# sch.net
KiCad netlist of a schematic drawn in EAGLE
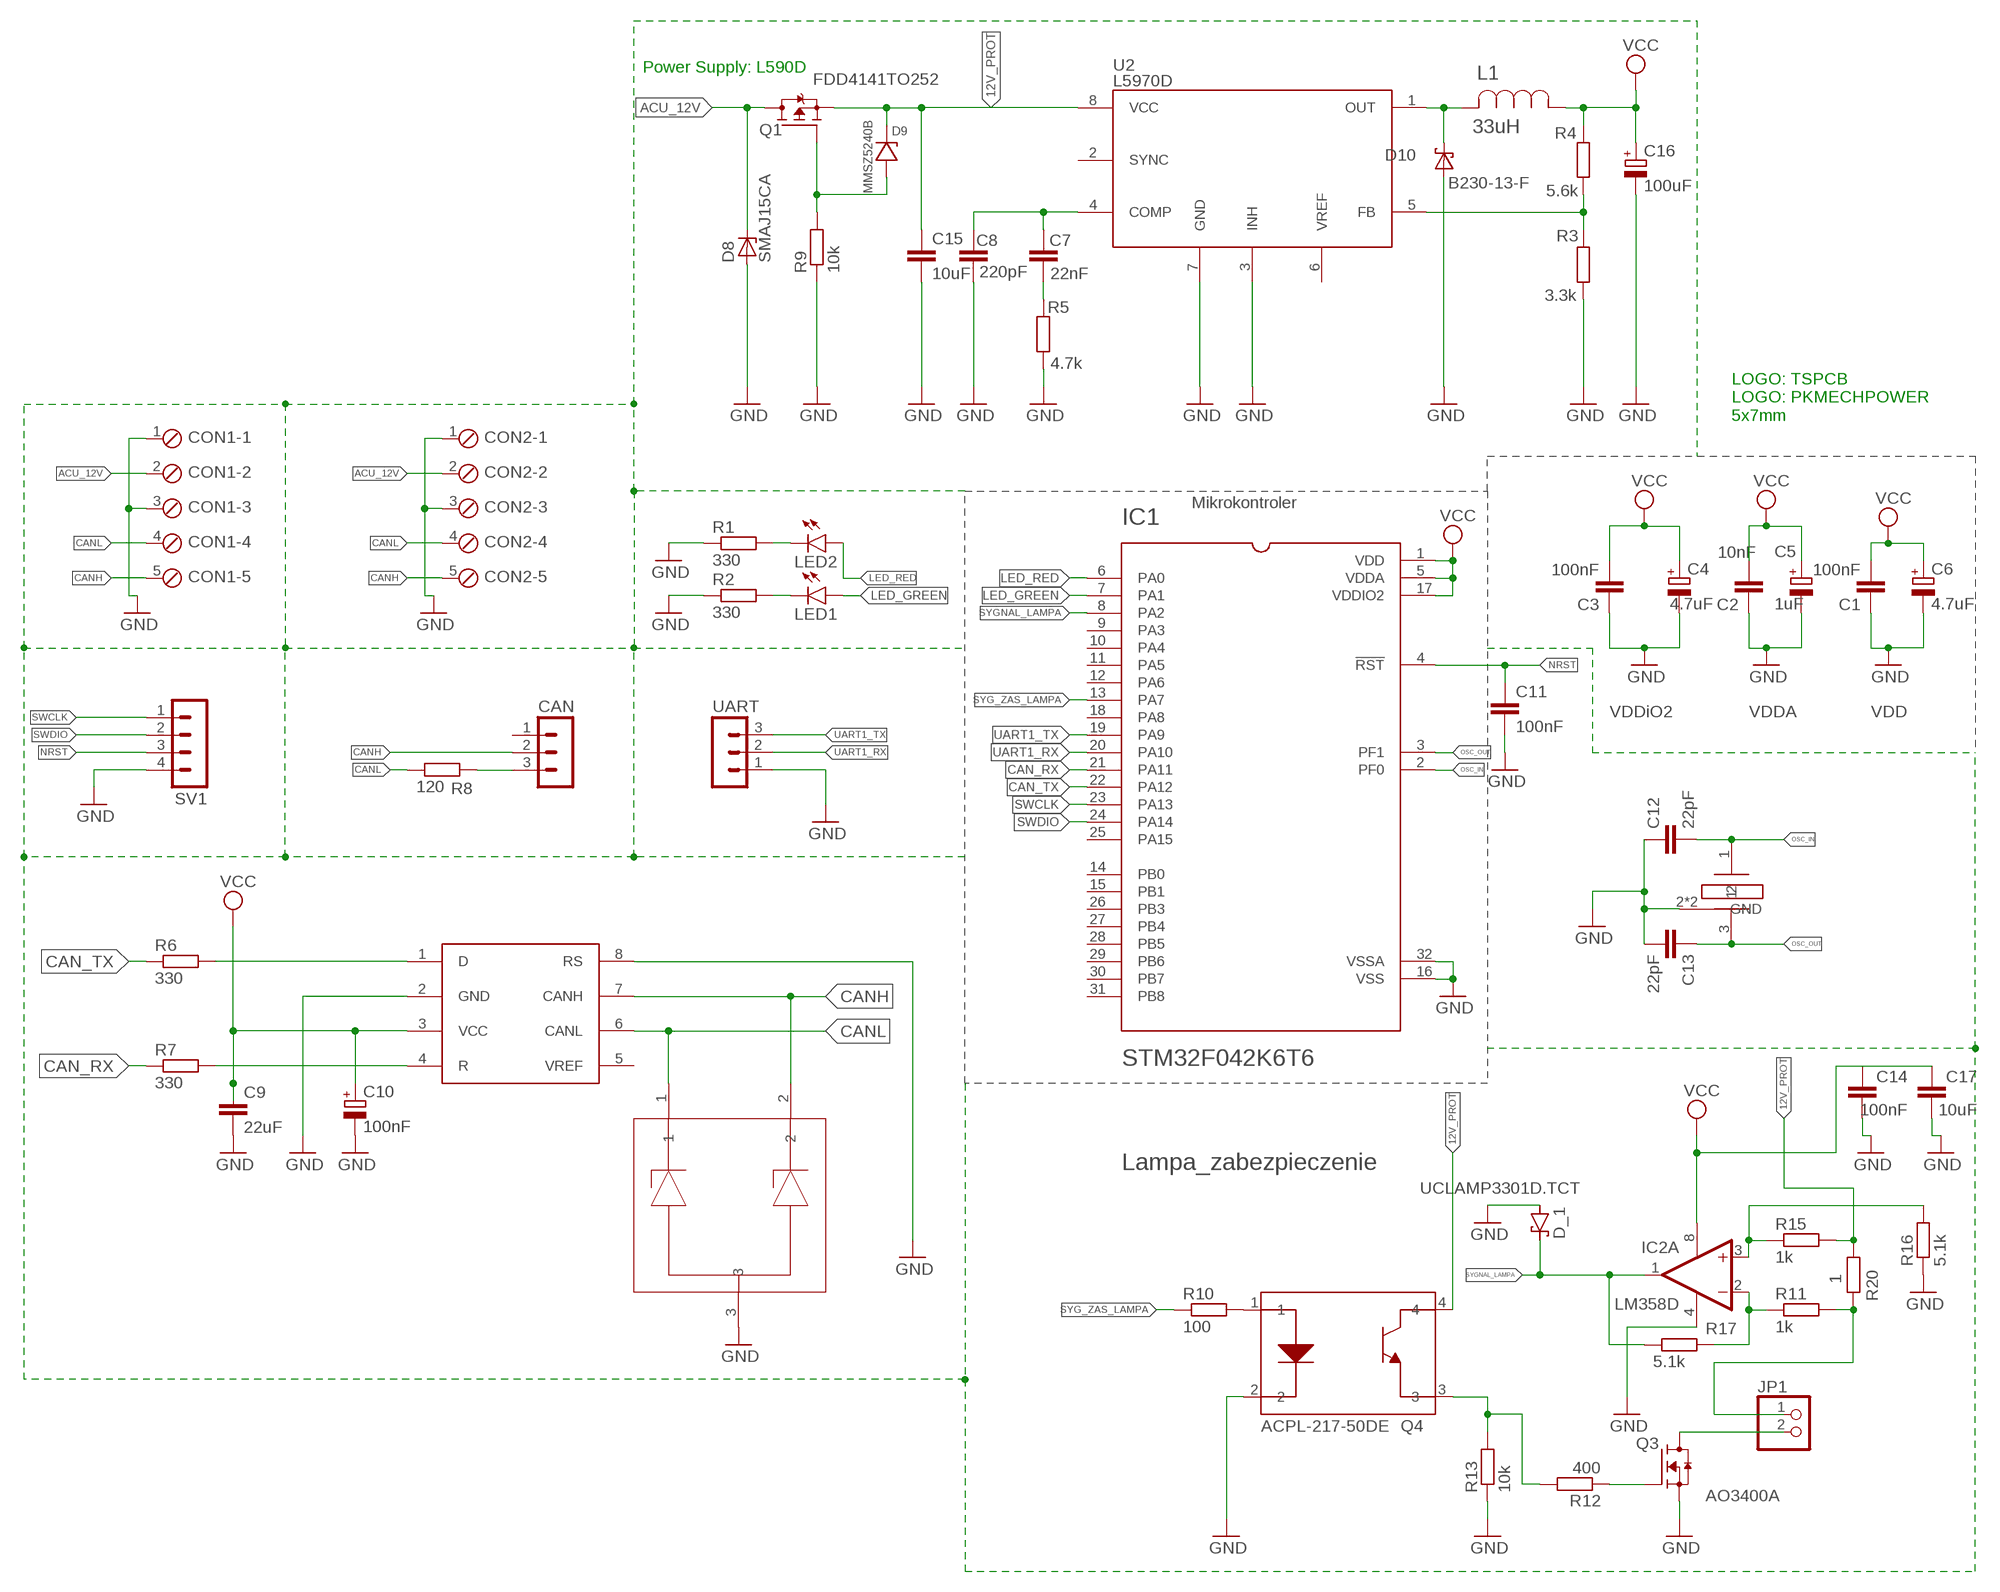
[diagram p0: schematic, sheet 1]

(export (version "E")
  (design (tool "Eeschema 10.0.6"))
  (components
    (comp (ref "C1")
      (value "100nF")
      (footprint "eagle-import:C0805")
      (libsource (lib "eagle-import") (part "C-EUC0805"))
    )
    (comp (ref "C2")
      (value "10nF")
      (footprint "eagle-import:C0805")
      (libsource (lib "eagle-import") (part "C-EUC0805"))
    )
    (comp (ref "C3")
      (value "100nF")
      (footprint "eagle-import:C0805")
      (libsource (lib "eagle-import") (part "C-EUC0805"))
    )
    (comp (ref "C4")
      (value "4.7uF")
      (footprint "eagle-import:SMC_C")
      (libsource (lib "eagle-import") (part "CPOL-EUSMCC"))
    )
    (comp (ref "C5")
      (value "1uF")
      (footprint "eagle-import:SMC_C")
      (libsource (lib "eagle-import") (part "CPOL-EUSMCC"))
    )
    (comp (ref "C6")
      (value "4.7uF")
      (footprint "eagle-import:SMC_C")
      (libsource (lib "eagle-import") (part "CPOL-EUSMCC"))
    )
    (comp (ref "C7")
      (value "22nF")
      (footprint "eagle-import:C0805")
      (libsource (lib "eagle-import") (part "C-EUC0805"))
    )
    (comp (ref "C8")
      (value "220pF")
      (footprint "eagle-import:C0805")
      (libsource (lib "eagle-import") (part "C-EUC0805"))
    )
    (comp (ref "C9")
      (value "22uF")
      (footprint "eagle-import:C0805")
      (libsource (lib "eagle-import") (part "C-EUC0805"))
    )
    (comp (ref "C10")
      (value "100nF")
      (footprint "eagle-import:SMC_C")
      (libsource (lib "eagle-import") (part "CPOL-EUSMCC"))
    )
    (comp (ref "C11")
      (value "100nF")
      (footprint "eagle-import:C0805")
      (libsource (lib "eagle-import") (part "C-EUC0805"))
    )
    (comp (ref "C12")
      (value "22pF")
      (footprint "eagle-import:C0805")
      (libsource (lib "eagle-import") (part "C-EUC0805"))
    )
    (comp (ref "C13")
      (value "22pF")
      (footprint "eagle-import:C0805")
      (libsource (lib "eagle-import") (part "C-EUC0805"))
    )
    (comp (ref "C14")
      (value "100nF")
      (footprint "eagle-import:C0805")
      (libsource (lib "eagle-import") (part "C-EUC0805"))
    )
    (comp (ref "C15")
      (value "10uF")
      (footprint "eagle-import:C1210")
      (libsource (lib "eagle-import") (part "C-EUC1210"))
    )
    (comp (ref "C16")
      (value "100uF")
      (footprint "eagle-import:SMC_D")
      (libsource (lib "eagle-import") (part "CPOL-EUSMCD"))
    )
    (comp (ref "C17")
      (value "10uF")
      (footprint "eagle-import:C0805")
      (libsource (lib "eagle-import") (part "C-EUC0805"))
    )
    (comp (ref "CAN")
      (value "MA03-1")
      (footprint "eagle-import:MA03-1")
      (libsource (lib "eagle-import") (part "MA03-1"))
    )
    (comp (ref "CON1")
      (value "MPT5")
      (footprint "eagle-import:5POL254")
      (libsource (lib "eagle-import") (part "MPT5"))
    )
    (comp (ref "CON2")
      (value "MPT5")
      (footprint "eagle-import:5POL254")
      (libsource (lib "eagle-import") (part "MPT5"))
    )
    (comp (ref "D8")
      (value "SMAJ15CA")
      (footprint "eagle-import:SMA")
      (fields (field (name "MF") "Nexperia USA") (field (name "MP") "PESD5V0X1UB"))
      (libsource (lib "eagle-import") (part "SMAJ15CA"))
    )
    (comp (ref "D9")
      (value "MMSZ5240B")
      (footprint "eagle-import:SOD123")
      (libsource (lib "eagle-import") (part "ZENER_01"))
    )
    (comp (ref "D10")
      (value "B230-13-F")
      (footprint "eagle-import:SMB")
      (libsource (lib "eagle-import") (part "B230-13-F"))
    )
    (comp (ref "D_1")
      (value "UCLAMP3301D.TCT")
      (footprint "eagle-import:SOD323")
      (libsource (lib "eagle-import") (part "UCLAMP3301D.TCT"))
    )
    (comp (ref "IC1")
      (value "STM32F042K6T6")
      (footprint "eagle-import:QFP80P900X900X160-32N")
      (fields (field (name "MF") "STMicroelectronics"))
      (libsource (lib "eagle-import") (part "STM32F042K6T6"))
    )
    (comp (ref "IC2")
      (value "LM358D")
      (footprint "eagle-import:SO08")
      (libsource (lib "eagle-import") (part "LM358D"))
    )
    (comp (ref "JP1")
      (value "PINHD-1X2")
      (footprint "eagle-import:1X02")
      (libsource (lib "eagle-import") (part "PINHD-1X2"))
    )
    (comp (ref "L1")
      (value "33uH")
      (footprint "eagle-import:INDM125125X600N")
      (fields (field (name "MF") "Coilcraft") (field (name "MP") "DR125-680-R"))
      (libsource (lib "eagle-import") (part "DR125-680-R"))
    )
    (comp (ref "LED1")
      (value "LEDCHIP-LED0805")
      (footprint "eagle-import:CHIP-LED0805")
      (libsource (lib "eagle-import") (part "LEDCHIP-LED0805"))
    )
    (comp (ref "LED2")
      (value "LEDCHIP-LED0805")
      (footprint "eagle-import:CHIP-LED0805")
      (libsource (lib "eagle-import") (part "LEDCHIP-LED0805"))
    )
    (comp (ref "Q1")
      (value "FDD4141TO252")
      (footprint "eagle-import:TO252")
      (libsource (lib "eagle-import") (part "FDD4141TO252"))
    )
    (comp (ref "Q3")
      (value "AO3400A")
      (footprint "eagle-import:SOT95P280X125-3N")
      (fields (field (name "MF") "Alpha &"))
      (libsource (lib "eagle-import") (part "AO3400A"))
    )
    (comp (ref "Q4")
      (value "ACPL-217-50DE")
      (footprint "eagle-import:SOIC127P700X220-4N")
      (fields (field (name "MF") "Broadcom / Avago"))
      (libsource (lib "eagle-import") (part "ACPL-217-50DE"))
    )
    (comp (ref "R1")
      (value "330")
      (footprint "eagle-import:R0805")
      (libsource (lib "eagle-import") (part "R-EU_R0805"))
    )
    (comp (ref "R2")
      (value "330")
      (footprint "eagle-import:R0805")
      (libsource (lib "eagle-import") (part "R-EU_R0805"))
    )
    (comp (ref "R3")
      (value "3.3k")
      (footprint "eagle-import:R0805")
      (libsource (lib "eagle-import") (part "R-EU_R0805"))
    )
    (comp (ref "R4")
      (value "5.6k")
      (footprint "eagle-import:R0805")
      (libsource (lib "eagle-import") (part "R-EU_R0805"))
    )
    (comp (ref "R5")
      (value "4.7k")
      (footprint "eagle-import:R0805")
      (libsource (lib "eagle-import") (part "R-EU_R0805"))
    )
    (comp (ref "R6")
      (value "330")
      (footprint "eagle-import:M0805")
      (libsource (lib "eagle-import") (part "R-EU_M0805"))
    )
    (comp (ref "R7")
      (value "330")
      (footprint "eagle-import:M0805")
      (libsource (lib "eagle-import") (part "R-EU_M0805"))
    )
    (comp (ref "R8")
      (value "120")
      (footprint "eagle-import:M0805")
      (libsource (lib "eagle-import") (part "R-EU_M0805"))
    )
    (comp (ref "R9")
      (value "10k")
      (footprint "eagle-import:R0805")
      (libsource (lib "eagle-import") (part "R-EU_R0805"))
    )
    (comp (ref "R10")
      (value "100")
      (footprint "eagle-import:M0805")
      (libsource (lib "eagle-import") (part "R-EU_M0805"))
    )
    (comp (ref "R11")
      (value "1k")
      (footprint "eagle-import:M0805")
      (libsource (lib "eagle-import") (part "R-EU_M0805"))
    )
    (comp (ref "R12")
      (value "400")
      (footprint "eagle-import:M0805")
      (libsource (lib "eagle-import") (part "R-EU_M0805"))
    )
    (comp (ref "R13")
      (value "10k")
      (footprint "eagle-import:M0805")
      (libsource (lib "eagle-import") (part "R-EU_M0805"))
    )
    (comp (ref "R15")
      (value "1k")
      (footprint "eagle-import:M0805")
      (libsource (lib "eagle-import") (part "R-EU_M0805"))
    )
    (comp (ref "R16")
      (value "5.1k")
      (footprint "eagle-import:M0805")
      (libsource (lib "eagle-import") (part "R-EU_M0805"))
    )
    (comp (ref "R17")
      (value "5.1k")
      (footprint "eagle-import:M0805")
      (libsource (lib "eagle-import") (part "R-EU_M0805"))
    )
    (comp (ref "R20")
      (value "1")
      (footprint "eagle-import:R2512")
      (libsource (lib "eagle-import") (part "R-EU_R2512"))
    )
    (comp (ref "SV1")
      (value "MA04-1")
      (footprint "eagle-import:MA04-1")
      (libsource (lib "eagle-import") (part "MA04-1"))
    )
    (comp (ref "U$1")
      (value "SN65HVD")
      (footprint "eagle-import:SO8")
      (libsource (lib "eagle-import") (part "SN65HVD"))
    )
    (comp (ref "U$2")
      (value "PESD3V3S2UT_")
      (footprint "eagle-import:SOT95P230X110-3N")
      (libsource (lib "eagle-import") (part "PESD3V3S2UT_"))
    )
    (comp (ref "U2")
      (value "L5970D")
      (footprint "eagle-import:SO-8")
      (fields (field (name "MF") "STMicroelectronics"))
      (libsource (lib "eagle-import") (part "L5970D"))
    )
    (comp (ref "UART")
      (value "MA03-1")
      (footprint "eagle-import:MA03-1")
      (libsource (lib "eagle-import") (part "MA03-1"))
    )
    (comp (ref "XTAL1")
      (value "CRYSTAL_SMDXT-324")
      (footprint "eagle-import:XT-324")
      (libsource (lib "eagle-import") (part "CRYSTAL_SMDXT-324"))
    )
  )
  (nets
    (net (code "1") (name "12V_PROT") (class "Default")
      (node (ref "C15") (pin "1") (pinfunction "1_1") (pintype "passive"))
      (node (ref "D9") (pin "1") (pinfunction "1_1") (pintype "bidirectional"))
      (node (ref "Q1") (pin "2") (pinfunction "S_2") (pintype "passive"))
      (node (ref "Q4") (pin "4") (pinfunction "4_4") (pintype "passive"))
      (node (ref "R15") (pin "2") (pinfunction "2_2") (pintype "passive"))
      (node (ref "R20") (pin "2") (pinfunction "2_2") (pintype "passive"))
      (node (ref "U2") (pin "8") (pinfunction "VCC_8") (pintype "bidirectional"))
    )
    (net (code "2") (name "ACU_12V") (class "Default")
      (node (ref "CON1") (pin "2") (pinfunction "1_2") (pintype "passive"))
      (node (ref "CON2") (pin "2") (pinfunction "1_2") (pintype "passive"))
      (node (ref "D8") (pin "1") (pinfunction "K_1") (pintype "passive"))
      (node (ref "Q1") (pin "3") (pinfunction "D_3") (pintype "passive"))
    )
    (net (code "3") (name "CANH") (class "Default")
      (node (ref "CAN") (pin "2") (pinfunction "2_2") (pintype "passive"))
      (node (ref "CON1") (pin "5") (pinfunction "1_5") (pintype "passive"))
      (node (ref "CON2") (pin "5") (pinfunction "1_5") (pintype "passive"))
      (node (ref "U$1") (pin "7") (pinfunction "CANH_7") (pintype "bidirectional"))
      (node (ref "U$2") (pin "2") (pinfunction "2_2") (pintype "bidirectional"))
    )
    (net (code "4") (name "CANL") (class "Default")
      (node (ref "CON1") (pin "4") (pinfunction "1_4") (pintype "passive"))
      (node (ref "CON2") (pin "4") (pinfunction "1_4") (pintype "passive"))
      (node (ref "R8") (pin "1") (pinfunction "1_1") (pintype "passive"))
      (node (ref "U$1") (pin "6") (pinfunction "CANL_6") (pintype "bidirectional"))
      (node (ref "U$2") (pin "1") (pinfunction "1_1") (pintype "bidirectional"))
    )
    (net (code "5") (name "CAN_RX") (class "Default")
      (node (ref "IC1") (pin "21") (pinfunction "PA11_21") (pintype "bidirectional"))
      (node (ref "R7") (pin "1") (pinfunction "1_1") (pintype "passive"))
    )
    (net (code "6") (name "CAN_TX") (class "Default")
      (node (ref "IC1") (pin "22") (pinfunction "PA12_22") (pintype "bidirectional"))
      (node (ref "R6") (pin "1") (pinfunction "1_1") (pintype "passive"))
    )
    (net (code "7") (name "GND") (class "Default")
      (node (ref "C1") (pin "1") (pinfunction "1_1") (pintype "passive"))
      (node (ref "C10") (pin "-") (pinfunction "-_-") (pintype "passive"))
      (node (ref "C11") (pin "2") (pinfunction "2_2") (pintype "passive"))
      (node (ref "C12") (pin "1") (pinfunction "1_1") (pintype "passive"))
      (node (ref "C13") (pin "2") (pinfunction "2_2") (pintype "passive"))
      (node (ref "C14") (pin "1") (pinfunction "1_1") (pintype "passive"))
      (node (ref "C15") (pin "2") (pinfunction "2_2") (pintype "passive"))
      (node (ref "C16") (pin "-") (pinfunction "-_-") (pintype "passive"))
      (node (ref "C17") (pin "1") (pinfunction "1_1") (pintype "passive"))
      (node (ref "C2") (pin "1") (pinfunction "1_1") (pintype "passive"))
      (node (ref "C3") (pin "1") (pinfunction "1_1") (pintype "passive"))
      (node (ref "C4") (pin "-") (pinfunction "-_-") (pintype "passive"))
      (node (ref "C5") (pin "-") (pinfunction "-_-") (pintype "passive"))
      (node (ref "C6") (pin "-") (pinfunction "-_-") (pintype "passive"))
      (node (ref "C8") (pin "1") (pinfunction "1_1") (pintype "passive"))
      (node (ref "C9") (pin "2") (pinfunction "2_2") (pintype "passive"))
      (node (ref "CON1") (pin "1") (pinfunction "1_1") (pintype "passive"))
      (node (ref "CON1") (pin "3") (pinfunction "1_3") (pintype "passive"))
      (node (ref "CON2") (pin "1") (pinfunction "1_1") (pintype "passive"))
      (node (ref "CON2") (pin "3") (pinfunction "1_3") (pintype "passive"))
      (node (ref "D10") (pin "2") (pinfunction "A_2") (pintype "passive"))
      (node (ref "D8") (pin "2") (pinfunction "A_2") (pintype "passive"))
      (node (ref "D_1") (pin "1") (pinfunction "A_1") (pintype "passive"))
      (node (ref "IC1") (pin "16") (pinfunction "VSS_16") (pintype "passive"))
      (node (ref "IC1") (pin "32") (pinfunction "VSSA_32") (pintype "passive"))
      (node (ref "IC2") (pin "4") (pinfunction "V-_4") (pintype "power_in"))
      (node (ref "Q3") (pin "2") (pinfunction "S_2") (pintype "passive"))
      (node (ref "Q4") (pin "2") (pinfunction "2_2") (pintype "passive"))
      (node (ref "R1") (pin "1") (pinfunction "1_1") (pintype "passive"))
      (node (ref "R13") (pin "1") (pinfunction "1_1") (pintype "passive"))
      (node (ref "R16") (pin "1") (pinfunction "1_1") (pintype "passive"))
      (node (ref "R2") (pin "1") (pinfunction "1_1") (pintype "passive"))
      (node (ref "R3") (pin "1") (pinfunction "1_1") (pintype "passive"))
      (node (ref "R5") (pin "1") (pinfunction "1_1") (pintype "passive"))
      (node (ref "R9") (pin "1") (pinfunction "1_1") (pintype "passive"))
      (node (ref "SV1") (pin "4") (pinfunction "4_4") (pintype "passive"))
      (node (ref "U$1") (pin "2") (pinfunction "GND_2") (pintype "bidirectional"))
      (node (ref "U$1") (pin "8") (pinfunction "RS_8") (pintype "bidirectional"))
      (node (ref "U$2") (pin "3") (pinfunction "3_3") (pintype "bidirectional"))
      (node (ref "U2") (pin "3") (pinfunction "INH_3") (pintype "bidirectional"))
      (node (ref "U2") (pin "7") (pinfunction "GND_7") (pintype "bidirectional"))
      (node (ref "UART") (pin "1") (pinfunction "1_1") (pintype "passive"))
      (node (ref "XTAL1") (pin "2") (pinfunction "GND_2") (pintype "bidirectional"))
      (node (ref "XTAL1") (pin "4") (pinfunction "GND_4") (pintype "bidirectional"))
    )
    (net (code "8") (name "LED_GREEN") (class "Default")
      (node (ref "IC1") (pin "7") (pinfunction "PA1_7") (pintype "bidirectional"))
      (node (ref "LED1") (pin "A") (pinfunction "A_A") (pintype "passive"))
    )
    (net (code "9") (name "LED_RED") (class "Default")
      (node (ref "IC1") (pin "6") (pinfunction "PA0_6") (pintype "bidirectional"))
      (node (ref "LED2") (pin "A") (pinfunction "A_A") (pintype "passive"))
    )
    (net (code "10") (name "NRST") (class "Default")
      (node (ref "C11") (pin "1") (pinfunction "1_1") (pintype "passive"))
      (node (ref "IC1") (pin "4") (pinfunction "~{RST}_4") (pintype "input"))
      (node (ref "SV1") (pin "3") (pinfunction "3_3") (pintype "passive"))
    )
    (net (code "11") (name "Net-(C7-Pad1)") (class "Default")
      (node (ref "C7") (pin "1") (pinfunction "1_1") (pintype "passive"))
      (node (ref "R5") (pin "2") (pinfunction "2_2") (pintype "passive"))
    )
    (net (code "12") (name "Net-(CAN-Pad3)") (class "Default")
      (node (ref "CAN") (pin "3") (pinfunction "3_3") (pintype "passive"))
      (node (ref "R8") (pin "2") (pinfunction "2_2") (pintype "passive"))
    )
    (net (code "13") (name "Net-(D10-K)") (class "Default")
      (node (ref "D10") (pin "1") (pinfunction "K_1") (pintype "passive"))
      (node (ref "L1") (pin "2") (pinfunction "2_2") (pintype "passive"))
      (node (ref "U2") (pin "1") (pinfunction "OUT_1") (pintype "bidirectional"))
    )
    (net (code "14") (name "Net-(IC2A-+IN)") (class "Default")
      (node (ref "IC2") (pin "3") (pinfunction "+IN_3") (pintype "input"))
      (node (ref "R15") (pin "1") (pinfunction "1_1") (pintype "passive"))
      (node (ref "R16") (pin "2") (pinfunction "2_2") (pintype "passive"))
    )
    (net (code "15") (name "Net-(IC2A--IN)") (class "Default")
      (node (ref "IC2") (pin "2") (pinfunction "-IN_2") (pintype "input"))
      (node (ref "R11") (pin "1") (pinfunction "1_1") (pintype "passive"))
      (node (ref "R17") (pin "2") (pinfunction "2_2") (pintype "passive"))
    )
    (net (code "16") (name "Net-(JP1-Pad1)") (class "Default")
      (node (ref "JP1") (pin "1") (pinfunction "1_1") (pintype "passive"))
      (node (ref "R11") (pin "2") (pinfunction "2_2") (pintype "passive"))
      (node (ref "R20") (pin "1") (pinfunction "1_1") (pintype "passive"))
    )
    (net (code "17") (name "Net-(LED1-PadC)") (class "Default")
      (node (ref "LED1") (pin "C") (pinfunction "C_C") (pintype "passive"))
      (node (ref "R2") (pin "2") (pinfunction "2_2") (pintype "passive"))
    )
    (net (code "18") (name "Net-(LED2-PadC)") (class "Default")
      (node (ref "LED2") (pin "C") (pinfunction "C_C") (pintype "passive"))
      (node (ref "R1") (pin "2") (pinfunction "2_2") (pintype "passive"))
    )
    (net (code "19") (name "Net-(Q1-G)") (class "Default")
      (node (ref "D9") (pin "2") (pinfunction "2_2") (pintype "bidirectional"))
      (node (ref "Q1") (pin "1") (pinfunction "G_1") (pintype "passive"))
      (node (ref "R9") (pin "2") (pinfunction "2_2") (pintype "passive"))
    )
    (net (code "20") (name "Net-(Q3-D)") (class "Default")
      (node (ref "JP1") (pin "2") (pinfunction "2_2") (pintype "passive"))
      (node (ref "Q3") (pin "3") (pinfunction "D_3") (pintype "passive"))
    )
    (net (code "21") (name "Net-(Q3-G)") (class "Default")
      (node (ref "Q3") (pin "1") (pinfunction "G_1") (pintype "passive"))
      (node (ref "R12") (pin "1") (pinfunction "1_1") (pintype "passive"))
    )
    (net (code "22") (name "Net-(Q4-Pad1)") (class "Default")
      (node (ref "Q4") (pin "1") (pinfunction "1_1") (pintype "passive"))
      (node (ref "R10") (pin "2") (pinfunction "2_2") (pintype "passive"))
    )
    (net (code "23") (name "Net-(Q4-Pad3)") (class "Default")
      (node (ref "Q4") (pin "3") (pinfunction "3_3") (pintype "passive"))
      (node (ref "R12") (pin "2") (pinfunction "2_2") (pintype "passive"))
      (node (ref "R13") (pin "2") (pinfunction "2_2") (pintype "passive"))
    )
    (net (code "24") (name "Net-(U$1-D)") (class "Default")
      (node (ref "R6") (pin "2") (pinfunction "2_2") (pintype "passive"))
      (node (ref "U$1") (pin "1") (pinfunction "D_1") (pintype "bidirectional"))
    )
    (net (code "25") (name "Net-(U$1-R)") (class "Default")
      (node (ref "R7") (pin "2") (pinfunction "2_2") (pintype "passive"))
      (node (ref "U$1") (pin "4") (pinfunction "R_4") (pintype "bidirectional"))
    )
    (net (code "26") (name "Net-(U2-COMP)") (class "Default")
      (node (ref "C7") (pin "2") (pinfunction "2_2") (pintype "passive"))
      (node (ref "C8") (pin "2") (pinfunction "2_2") (pintype "passive"))
      (node (ref "U2") (pin "4") (pinfunction "COMP_4") (pintype "bidirectional"))
    )
    (net (code "27") (name "Net-(U2-FB)") (class "Default")
      (node (ref "R3") (pin "2") (pinfunction "2_2") (pintype "passive"))
      (node (ref "R4") (pin "1") (pinfunction "1_1") (pintype "passive"))
      (node (ref "U2") (pin "5") (pinfunction "FB_5") (pintype "bidirectional"))
    )
    (net (code "28") (name "OSC_IN") (class "Default")
      (node (ref "C12") (pin "2") (pinfunction "2_2") (pintype "passive"))
      (node (ref "IC1") (pin "2") (pinfunction "PF0_2") (pintype "bidirectional"))
      (node (ref "XTAL1") (pin "1") (pinfunction "1_1") (pintype "bidirectional"))
    )
    (net (code "29") (name "OSC_OUT") (class "Default")
      (node (ref "C13") (pin "1") (pinfunction "1_1") (pintype "passive"))
      (node (ref "IC1") (pin "3") (pinfunction "PF1_3") (pintype "bidirectional"))
      (node (ref "XTAL1") (pin "3") (pinfunction "2_3") (pintype "bidirectional"))
    )
    (net (code "30") (name "SWCLK") (class "Default")
      (node (ref "IC1") (pin "23") (pinfunction "PA13_23") (pintype "bidirectional"))
      (node (ref "SV1") (pin "1") (pinfunction "1_1") (pintype "passive"))
    )
    (net (code "31") (name "SWDIO") (class "Default")
      (node (ref "IC1") (pin "24") (pinfunction "PA14_24") (pintype "bidirectional"))
      (node (ref "SV1") (pin "2") (pinfunction "2_2") (pintype "passive"))
    )
    (net (code "32") (name "SYGNAL_LAMPA") (class "Default")
      (node (ref "D_1") (pin "2") (pinfunction "C_2") (pintype "passive"))
      (node (ref "IC1") (pin "8") (pinfunction "PA2_8") (pintype "bidirectional"))
      (node (ref "IC2") (pin "1") (pinfunction "OUT_1") (pintype "output"))
      (node (ref "R17") (pin "1") (pinfunction "1_1") (pintype "passive"))
    )
    (net (code "33") (name "SYG_ZAS_LAMPA") (class "Default")
      (node (ref "IC1") (pin "13") (pinfunction "PA7_13") (pintype "bidirectional"))
      (node (ref "R10") (pin "1") (pinfunction "1_1") (pintype "passive"))
    )
    (net (code "34") (name "UART1_RX") (class "Default")
      (node (ref "IC1") (pin "20") (pinfunction "PA10_20") (pintype "bidirectional"))
      (node (ref "UART") (pin "2") (pinfunction "2_2") (pintype "passive"))
    )
    (net (code "35") (name "UART1_TX") (class "Default")
      (node (ref "IC1") (pin "19") (pinfunction "PA9_19") (pintype "bidirectional"))
      (node (ref "UART") (pin "3") (pinfunction "3_3") (pintype "passive"))
    )
    (net (code "36") (name "VCC") (class "Default")
      (node (ref "C1") (pin "2") (pinfunction "2_2") (pintype "passive"))
      (node (ref "C10") (pin "+") (pinfunction "+_+") (pintype "passive"))
      (node (ref "C14") (pin "2") (pinfunction "2_2") (pintype "passive"))
      (node (ref "C16") (pin "+") (pinfunction "+_+") (pintype "passive"))
      (node (ref "C17") (pin "2") (pinfunction "2_2") (pintype "passive"))
      (node (ref "C2") (pin "2") (pinfunction "2_2") (pintype "passive"))
      (node (ref "C3") (pin "2") (pinfunction "2_2") (pintype "passive"))
      (node (ref "C4") (pin "+") (pinfunction "+_+") (pintype "passive"))
      (node (ref "C5") (pin "+") (pinfunction "+_+") (pintype "passive"))
      (node (ref "C6") (pin "+") (pinfunction "+_+") (pintype "passive"))
      (node (ref "C9") (pin "1") (pinfunction "1_1") (pintype "passive"))
      (node (ref "IC1") (pin "1") (pinfunction "VDD_1") (pintype "power_in"))
      (node (ref "IC1") (pin "17") (pinfunction "VDDIO2_17") (pintype "power_in"))
      (node (ref "IC1") (pin "5") (pinfunction "VDDA_5") (pintype "power_in"))
      (node (ref "IC2") (pin "8") (pinfunction "V+_8") (pintype "power_in"))
      (node (ref "L1") (pin "1") (pinfunction "1_1") (pintype "passive"))
      (node (ref "R4") (pin "2") (pinfunction "2_2") (pintype "passive"))
      (node (ref "U$1") (pin "3") (pinfunction "VCC_3") (pintype "bidirectional"))
    )
    (net (code "37") (name "unconnected-(CAN-Pad1)") (class "Default")
      (node (ref "CAN") (pin "1") (pinfunction "1_1") (pintype "passive"))
    )
    (net (code "38") (name "unconnected-(IC1-PA3-Pad9)") (class "Default")
      (node (ref "IC1") (pin "9") (pinfunction "PA3_9") (pintype "bidirectional"))
    )
    (net (code "39") (name "unconnected-(IC1-PA4-Pad10)") (class "Default")
      (node (ref "IC1") (pin "10") (pinfunction "PA4_10") (pintype "bidirectional"))
    )
    (net (code "40") (name "unconnected-(IC1-PA5-Pad11)") (class "Default")
      (node (ref "IC1") (pin "11") (pinfunction "PA5_11") (pintype "bidirectional"))
    )
    (net (code "41") (name "unconnected-(IC1-PA6-Pad12)") (class "Default")
      (node (ref "IC1") (pin "12") (pinfunction "PA6_12") (pintype "bidirectional"))
    )
    (net (code "42") (name "unconnected-(IC1-PA8-Pad18)") (class "Default")
      (node (ref "IC1") (pin "18") (pinfunction "PA8_18") (pintype "bidirectional"))
    )
    (net (code "43") (name "unconnected-(IC1-PA15-Pad25)") (class "Default")
      (node (ref "IC1") (pin "25") (pinfunction "PA15_25") (pintype "bidirectional"))
    )
    (net (code "44") (name "unconnected-(IC1-PB0-Pad14)") (class "Default")
      (node (ref "IC1") (pin "14") (pinfunction "PB0_14") (pintype "bidirectional"))
    )
    (net (code "45") (name "unconnected-(IC1-PB1-Pad15)") (class "Default")
      (node (ref "IC1") (pin "15") (pinfunction "PB1_15") (pintype "bidirectional"))
    )
    (net (code "46") (name "unconnected-(IC1-PB3-Pad26)") (class "Default")
      (node (ref "IC1") (pin "26") (pinfunction "PB3_26") (pintype "bidirectional"))
    )
    (net (code "47") (name "unconnected-(IC1-PB4-Pad27)") (class "Default")
      (node (ref "IC1") (pin "27") (pinfunction "PB4_27") (pintype "bidirectional"))
    )
    (net (code "48") (name "unconnected-(IC1-PB5-Pad28)") (class "Default")
      (node (ref "IC1") (pin "28") (pinfunction "PB5_28") (pintype "bidirectional"))
    )
    (net (code "49") (name "unconnected-(IC1-PB6-Pad29)") (class "Default")
      (node (ref "IC1") (pin "29") (pinfunction "PB6_29") (pintype "bidirectional"))
    )
    (net (code "50") (name "unconnected-(IC1-PB7-Pad30)") (class "Default")
      (node (ref "IC1") (pin "30") (pinfunction "PB7_30") (pintype "bidirectional"))
    )
    (net (code "51") (name "unconnected-(IC1-PB8-Pad31)") (class "Default")
      (node (ref "IC1") (pin "31") (pinfunction "PB8_31") (pintype "bidirectional"))
    )
    (net (code "52") (name "unconnected-(U$1-VREF-Pad5)") (class "Default")
      (node (ref "U$1") (pin "5") (pinfunction "VREF_5") (pintype "bidirectional"))
    )
    (net (code "53") (name "unconnected-(U2-SYNC-Pad2)") (class "Default")
      (node (ref "U2") (pin "2") (pinfunction "SYNC_2") (pintype "bidirectional"))
    )
    (net (code "54") (name "unconnected-(U2-VREF-Pad6)") (class "Default")
      (node (ref "U2") (pin "6") (pinfunction "VREF_6") (pintype "bidirectional"))
    )
  )
)
